# Linear_camera_schematic.net
KiCad netlist of a schematic drawn in Altium Designer
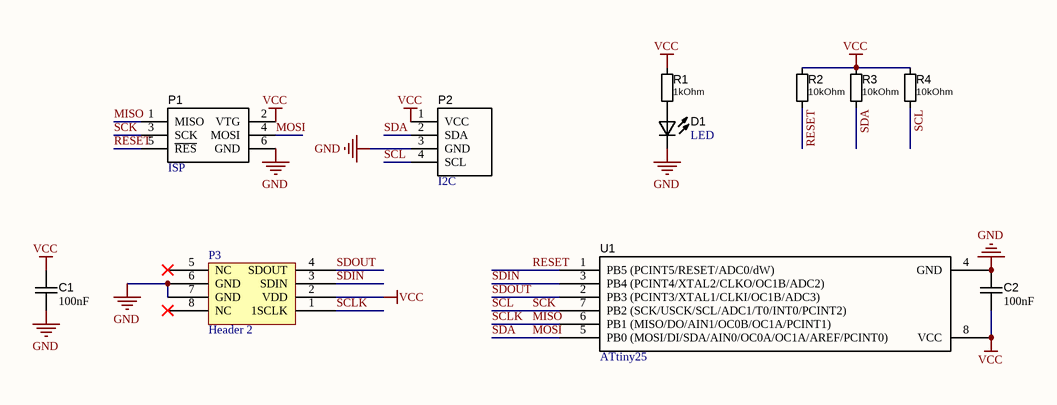
[diagram p0: Linear_camera_schematic.SchDoc]

(export (version "E")
  (design (tool "Eeschema 10.0.6"))
  (components
    (comp (ref "C1")
      (value "100nF")
      (footprint "C/0805")
      (description "Capacitor")
      (fields (field (name "Comment") "C") (field (name "PUBLISHER") "Altium Limited"))
      (libsource (lib "andylib") (part "C"))
    )
    (comp (ref "C2")
      (value "100nF")
      (footprint "C/0805")
      (description "Capacitor")
      (fields (field (name "Comment") "C") (field (name "PUBLISHER") "Altium Limited"))
      (libsource (lib "andylib") (part "C"))
    )
    (comp (ref "D1")
      (value "LED")
      (footprint "LED-2012[0805]")
      (fields (field (name "PUBLISHER") "Altium Limited"))
      (libsource (lib "andylib") (part "LED"))
    )
    (comp (ref "P1")
      (value "ISP")
      (footprint "HEADER2X3")
      (description "AVR ISP 6pin")
      (fields (field (name "PUBLISHER") "Altium Limited"))
      (libsource (lib "andylib") (part "AVR ISP 6pin"))
    )
    (comp (ref "P2")
      (value "I2C")
      (footprint "TYCO/215079-4")
      (description "Micromatch I2C Connector")
      (libsource (lib "andylib") (part "Micromatch-I2C"))
    )
    (comp (ref "P3")
      (value "Header 2")
      (footprint "TSL3301CL")
      (description "Header, 2-Pin")
      (fields (field (name "PUBLISHER") "Altium Limited"))
      (libsource (lib "marcolib") (part "TSL3301CL"))
    )
    (comp (ref "R1")
      (value "1kOhm")
      (footprint "R/0805")
      (description "Resistor")
      (fields (field (name "PUBLISHER") "Altium Limited"))
      (libsource (lib "andylib") (part "R"))
    )
    (comp (ref "R2")
      (value "10kOhm")
      (footprint "R/0805")
      (description "Resistor")
      (fields (field (name "PUBLISHER") "Altium Limited"))
      (libsource (lib "andylib") (part "R"))
    )
    (comp (ref "R3")
      (value "10kOhm")
      (footprint "R/0805")
      (description "Resistor")
      (fields (field (name "PUBLISHER") "Altium Limited"))
      (libsource (lib "andylib") (part "R"))
    )
    (comp (ref "R4")
      (value "10kOhm")
      (footprint "R/0805")
      (description "Resistor")
      (fields (field (name "PUBLISHER") "Altium Limited"))
      (libsource (lib "andylib") (part "R"))
    )
    (comp (ref "U1")
      (value "ATtiny25")
      (footprint "SOIC8 - ATtiny25")
      (libsource (lib "andylib") (part "ATtiny25"))
    )
  )
  (nets
    (net (code "1") (name "/MISO") (class "Default")
      (node (ref "P1") (pin "1") (pinfunction "MISO_1") (pintype "passive"))
      (node (ref "P3") (pin "1") (pinfunction "1SCLK_1") (pintype "passive"))
      (node (ref "U1") (pin "6") (pinfunction "PB1_(MISO/DO/AIN1/OC0B/OC1A/PCINT1)_6") (pintype "passive"))
    )
    (net (code "2") (name "/MOSI") (class "Default")
      (node (ref "P1") (pin "4") (pinfunction "MOSI_4") (pintype "passive"))
      (node (ref "P2") (pin "2") (pinfunction "SDA_2") (pintype "passive"))
      (node (ref "R3") (pin "1") (pinfunction "1_1") (pintype "passive"))
      (node (ref "U1") (pin "5") (pinfunction "PB0_(MOSI/DI/SDA/AIN0/OC0A/OC1A/AREF/PCINT0)_5") (pintype "passive"))
    )
    (net (code "3") (name "/RESET") (class "Default")
      (node (ref "P1") (pin "5") (pinfunction "~{RES}_5") (pintype "passive"))
      (node (ref "R2") (pin "1") (pinfunction "1_1") (pintype "passive"))
      (node (ref "U1") (pin "1") (pinfunction "PB5_(PCINT5/RESET/ADC0/dW)_1") (pintype "passive"))
    )
    (net (code "4") (name "/SCK") (class "Default")
      (node (ref "P1") (pin "3") (pinfunction "SCK_3") (pintype "passive"))
      (node (ref "P2") (pin "4") (pinfunction "SCL_4") (pintype "passive"))
      (node (ref "R4") (pin "1") (pinfunction "1_1") (pintype "passive"))
      (node (ref "U1") (pin "7") (pinfunction "PB2_(SCK/USCK/SCL/ADC1/T0/INT0/PCINT2)_7") (pintype "passive"))
    )
    (net (code "5") (name "/SDIN") (class "Default")
      (node (ref "P3") (pin "3") (pinfunction "SDIN_3") (pintype "passive"))
      (node (ref "U1") (pin "3") (pinfunction "PB4_(PCINT4/XTAL2/CLKO/OC1B/ADC2)_3") (pintype "passive"))
    )
    (net (code "6") (name "/SDOUT") (class "Default")
      (node (ref "P3") (pin "4") (pinfunction "SDOUT_4") (pintype "passive"))
      (node (ref "U1") (pin "2") (pinfunction "PB3_(PCINT3/XTAL1/CLKI/OC1B/ADC3)_2") (pintype "passive"))
    )
    (net (code "7") (name "GND") (class "Default")
      (node (ref "C1") (pin "1") (pinfunction "1_1") (pintype "passive"))
      (node (ref "C2") (pin "2") (pinfunction "2_2") (pintype "passive"))
      (node (ref "D1") (pin "K") (pinfunction "K_K") (pintype "passive"))
      (node (ref "P1") (pin "6") (pinfunction "GND_6") (pintype "passive"))
      (node (ref "P2") (pin "3") (pinfunction "GND_3") (pintype "passive"))
      (node (ref "P3") (pin "6") (pinfunction "GND_6") (pintype "passive"))
      (node (ref "P3") (pin "7") (pinfunction "GND_7") (pintype "passive"))
      (node (ref "U1") (pin "4") (pinfunction "GND_4") (pintype "passive"))
    )
    (net (code "8") (name "Net-(D1-PadA)") (class "Default")
      (node (ref "D1") (pin "A") (pinfunction "A_A") (pintype "passive"))
      (node (ref "R1") (pin "1") (pinfunction "1_1") (pintype "passive"))
    )
    (net (code "9") (name "VCC") (class "Default")
      (node (ref "C1") (pin "2") (pinfunction "2_2") (pintype "passive"))
      (node (ref "C2") (pin "1") (pinfunction "1_1") (pintype "passive"))
      (node (ref "P1") (pin "2") (pinfunction "VTG_2") (pintype "passive"))
      (node (ref "P2") (pin "1") (pinfunction "VCC_1") (pintype "passive"))
      (node (ref "P3") (pin "2") (pinfunction "VDD_2") (pintype "passive"))
      (node (ref "R1") (pin "2") (pinfunction "2_2") (pintype "passive"))
      (node (ref "R2") (pin "2") (pinfunction "2_2") (pintype "passive"))
      (node (ref "R3") (pin "2") (pinfunction "2_2") (pintype "passive"))
      (node (ref "R4") (pin "2") (pinfunction "2_2") (pintype "passive"))
      (node (ref "U1") (pin "8") (pinfunction "VCC_8") (pintype "passive"))
    )
    (net (code "10") (name "unconnected-(P3-NC-Pad5)") (class "Default")
      (node (ref "P3") (pin "5") (pinfunction "NC_5") (pintype "passive+no_connect"))
    )
    (net (code "11") (name "unconnected-(P3-NC-Pad8)") (class "Default")
      (node (ref "P3") (pin "8") (pinfunction "NC_8") (pintype "passive+no_connect"))
    )
  )
)
